# Arm_control_pull.net
KiCad netlist of a schematic drawn in Altium Designer
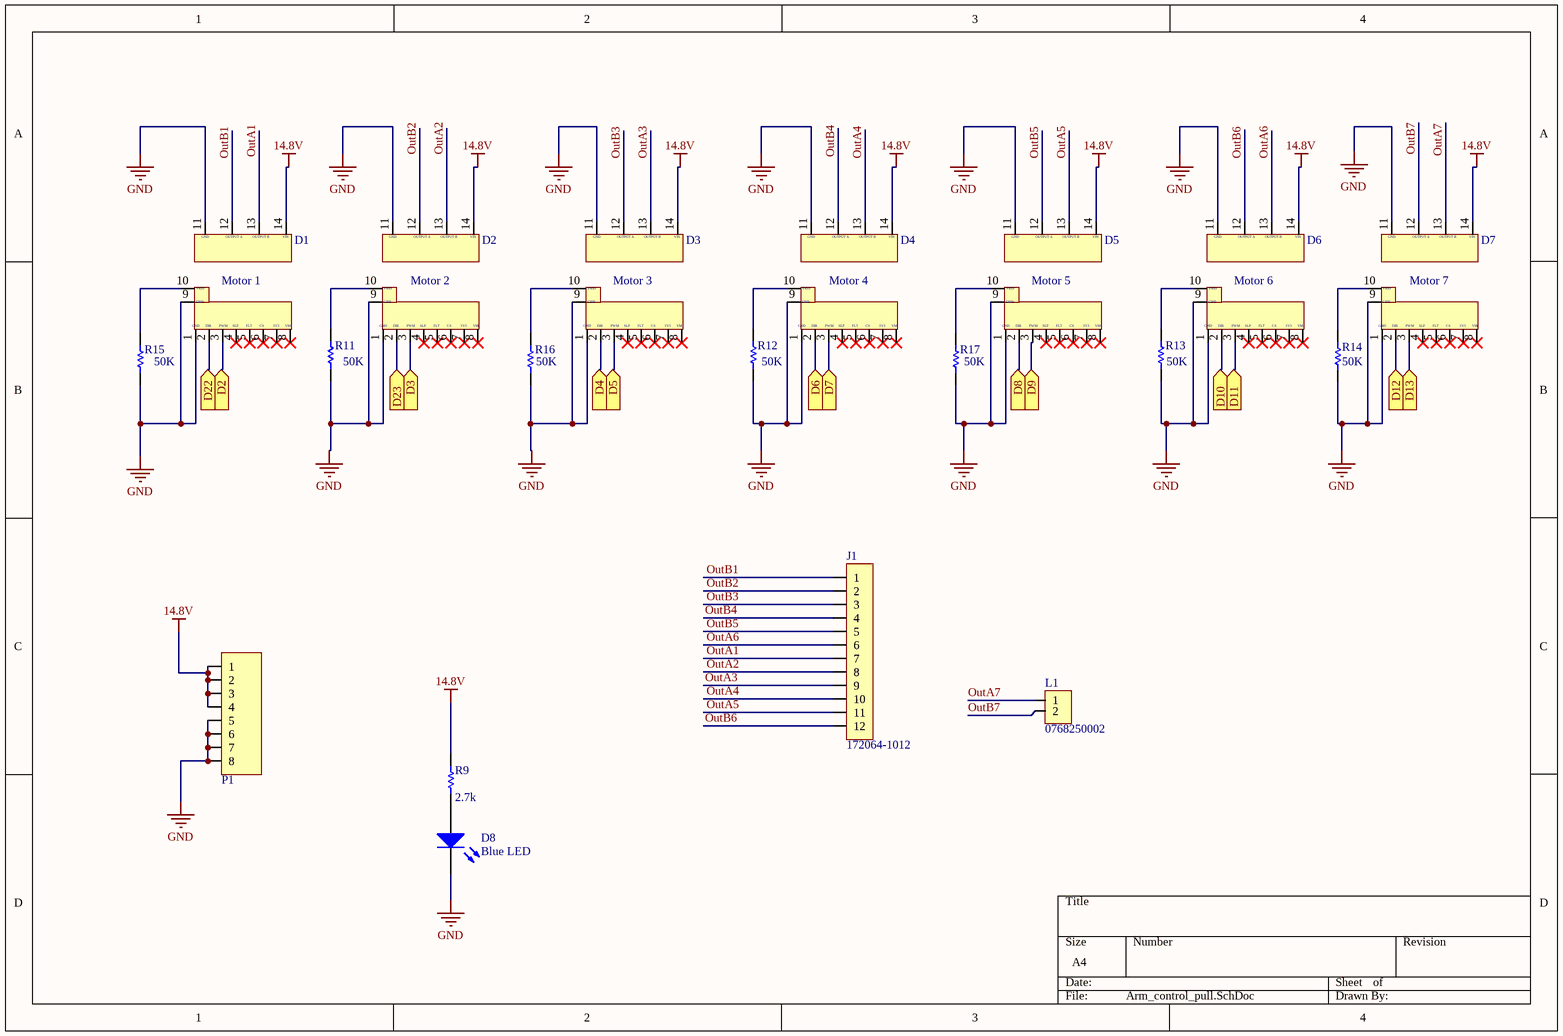
[diagram p0: Arm_control_pull.SchDoc]

(export (version "E")
  (design (tool "Eeschema 10.0.6"))
  (components
    (comp (ref "D1")
      (value "Pololu G2 High-Power Motor Driver 18v25")
      (footprint "POLOLU 18V25")
      (libsource (lib "RSX_Modules") (part "Pololu G2 High-Power Motor Driver 18v25"))
    )
    (comp (ref "D2")
      (value "Pololu G2 High-Power Motor Driver 18v25")
      (footprint "POLOLU 18V25")
      (libsource (lib "RSX_Modules") (part "Pololu G2 High-Power Motor Driver 18v25"))
    )
    (comp (ref "D3")
      (value "Pololu G2 High-Power Motor Driver 18v25")
      (footprint "POLOLU 18V25")
      (libsource (lib "RSX_Modules") (part "Pololu G2 High-Power Motor Driver 18v25"))
    )
    (comp (ref "D4")
      (value "Pololu G2 High-Power Motor Driver 18v25")
      (footprint "POLOLU 18V25")
      (libsource (lib "RSX_Modules") (part "Pololu G2 High-Power Motor Driver 18v25"))
    )
    (comp (ref "D5")
      (value "Pololu G2 High-Power Motor Driver 18v25")
      (footprint "POLOLU 18V25")
      (libsource (lib "RSX_Modules") (part "Pololu G2 High-Power Motor Driver 18v25"))
    )
    (comp (ref "D6")
      (value "Pololu G2 High-Power Motor Driver 18v25")
      (footprint "POLOLU 18V25")
      (libsource (lib "RSX_Modules") (part "Pololu G2 High-Power Motor Driver 18v25"))
    )
    (comp (ref "D7")
      (value "Pololu G2 High-Power Motor Driver 18v25")
      (footprint "POLOLU 18V25")
      (libsource (lib "RSX_Modules") (part "Pololu G2 High-Power Motor Driver 18v25"))
    )
    (comp (ref "D8")
      (value "Blue LED")
      (footprint "LTST-C171TBKT")
      (libsource (lib "RSX_Diodes") (part "Blue LED"))
    )
    (comp (ref "J1")
      (value "172064-1012")
      (footprint "172064-1012")
      (description "Conn Shrouded Header HDR 12 POS 5.7mm Solder RA Thru-Hole Tray")
      (libsource (lib "RSX_Connectors") (part "172064-1012"))
    )
    (comp (ref "L1")
      (value "0768250002")
      (footprint "MOLEX 0768250002")
      (description "Conn Power HDR 2 POS 5.7mm Solder RA Thru-Hole 2 Terminal 1 Port")
      (libsource (lib "RSX_Connectors") (part "0768250002"))
    )
    (comp (ref "P1")
      (value "Mini-Fit Jr 8 Pos RA")
      (footprint "MOLEX 172065-0208")
      (libsource (lib "RSX_Connectors") (part "Molex Mega-Fit 8pos Vert"))
    )
    (comp (ref "R9")
      (value "2.7k")
      (footprint "RESC1608X06N_0603")
      (description "Resistor")
      (fields (field (name "Comment") "Res1") (field (name "PUBLISHER") "Altium Limited"))
      (libsource (lib "RSX_Resistors") (part "Res1"))
    )
    (comp (ref "R11")
      (value "50K")
      (footprint "RESC1608X06N_0603")
      (description "Resistor")
      (fields (field (name "Comment") "Res1") (field (name "PUBLISHER") "Altium Limited"))
      (libsource (lib "RSX_Resistors") (part "Res1"))
    )
    (comp (ref "R12")
      (value "50K")
      (footprint "RESC1608X06N_0603")
      (description "Resistor")
      (fields (field (name "Comment") "Res1") (field (name "PUBLISHER") "Altium Limited"))
      (libsource (lib "RSX_Resistors") (part "Res1"))
    )
    (comp (ref "R13")
      (value "50K")
      (footprint "RESC1608X06N_0603")
      (description "Resistor")
      (fields (field (name "Comment") "Res1") (field (name "PUBLISHER") "Altium Limited"))
      (libsource (lib "RSX_Resistors") (part "Res1"))
    )
    (comp (ref "R14")
      (value "50K")
      (footprint "RESC1608X06N_0603")
      (description "Resistor")
      (fields (field (name "Comment") "Res1") (field (name "PUBLISHER") "Altium Limited"))
      (libsource (lib "RSX_Resistors") (part "Res1"))
    )
    (comp (ref "R15")
      (value "50K")
      (footprint "RESC1608X06N_0603")
      (description "Resistor")
      (fields (field (name "Comment") "Res1") (field (name "PUBLISHER") "Altium Limited"))
      (libsource (lib "RSX_Resistors") (part "Res1"))
    )
    (comp (ref "R16")
      (value "50K")
      (footprint "RESC1608X06N_0603")
      (description "Resistor")
      (fields (field (name "Comment") "Res1") (field (name "PUBLISHER") "Altium Limited"))
      (libsource (lib "RSX_Resistors") (part "Res1"))
    )
    (comp (ref "R17")
      (value "50K")
      (footprint "RESC1608X06N_0603")
      (description "Resistor")
      (fields (field (name "Comment") "Res1") (field (name "PUBLISHER") "Altium Limited"))
      (libsource (lib "RSX_Resistors") (part "Res1"))
    )
  )
  (nets
    (net (code "2") (name "/D2") (class "Default")
      (node (ref "D1") (pin "3") (pinfunction "3_3") (pintype "passive"))
    )
    (net (code "3") (name "/D3") (class "Default")
      (node (ref "D2") (pin "3") (pinfunction "3_3") (pintype "passive"))
    )
    (net (code "4") (name "/D4") (class "Default")
      (node (ref "D3") (pin "2") (pinfunction "2_2") (pintype "passive"))
    )
    (net (code "5") (name "/D5") (class "Default")
      (node (ref "D3") (pin "3") (pinfunction "3_3") (pintype "passive"))
    )
    (net (code "6") (name "/D6") (class "Default")
      (node (ref "D4") (pin "2") (pinfunction "2_2") (pintype "passive"))
    )
    (net (code "7") (name "/D7") (class "Default")
      (node (ref "D4") (pin "3") (pinfunction "3_3") (pintype "passive"))
    )
    (net (code "8") (name "/D8") (class "Default")
      (node (ref "D5") (pin "2") (pinfunction "2_2") (pintype "passive"))
    )
    (net (code "9") (name "/D9") (class "Default")
      (node (ref "D5") (pin "3") (pinfunction "3_3") (pintype "passive"))
    )
    (net (code "10") (name "/D10") (class "Default")
      (node (ref "D6") (pin "2") (pinfunction "2_2") (pintype "passive"))
    )
    (net (code "11") (name "/D11") (class "Default")
      (node (ref "D6") (pin "3") (pinfunction "3_3") (pintype "passive"))
    )
    (net (code "12") (name "/D12") (class "Default")
      (node (ref "D7") (pin "2") (pinfunction "2_2") (pintype "passive"))
    )
    (net (code "13") (name "/D13") (class "Default")
      (node (ref "D7") (pin "3") (pinfunction "3_3") (pintype "passive"))
    )
    (net (code "14") (name "/D22") (class "Default")
      (node (ref "D1") (pin "2") (pinfunction "2_2") (pintype "passive"))
    )
    (net (code "15") (name "/D23") (class "Default")
      (node (ref "D2") (pin "2") (pinfunction "2_2") (pintype "passive"))
    )
    (net (code "16") (name "/OutA1") (class "Default")
      (node (ref "D1") (pin "13") (pinfunction "13_13") (pintype "passive"))
      (node (ref "J1") (pin "7") (pinfunction "7_7") (pintype "passive"))
    )
    (net (code "17") (name "/OutA2") (class "Default")
      (node (ref "D2") (pin "13") (pinfunction "13_13") (pintype "passive"))
      (node (ref "J1") (pin "8") (pinfunction "8_8") (pintype "passive"))
    )
    (net (code "18") (name "/OutA3") (class "Default")
      (node (ref "D3") (pin "13") (pinfunction "13_13") (pintype "passive"))
      (node (ref "J1") (pin "9") (pinfunction "9_9") (pintype "passive"))
    )
    (net (code "19") (name "/OutA4") (class "Default")
      (node (ref "D4") (pin "13") (pinfunction "13_13") (pintype "passive"))
      (node (ref "J1") (pin "10") (pinfunction "10_10") (pintype "passive"))
    )
    (net (code "20") (name "/OutA5") (class "Default")
      (node (ref "D5") (pin "13") (pinfunction "13_13") (pintype "passive"))
      (node (ref "J1") (pin "11") (pinfunction "11_11") (pintype "passive"))
    )
    (net (code "21") (name "/OutA6") (class "Default")
      (node (ref "D6") (pin "13") (pinfunction "13_13") (pintype "passive"))
      (node (ref "J1") (pin "6") (pinfunction "6_6") (pintype "passive"))
    )
    (net (code "22") (name "/OutA7") (class "Default")
      (node (ref "D7") (pin "13") (pinfunction "13_13") (pintype "passive"))
      (node (ref "L1") (pin "1") (pinfunction "1_1") (pintype "passive"))
    )
    (net (code "23") (name "/OutB1") (class "Default")
      (node (ref "D1") (pin "12") (pinfunction "12_12") (pintype "passive"))
      (node (ref "J1") (pin "1") (pinfunction "1_1") (pintype "passive"))
    )
    (net (code "24") (name "/OutB2") (class "Default")
      (node (ref "D2") (pin "12") (pinfunction "12_12") (pintype "passive"))
      (node (ref "J1") (pin "2") (pinfunction "2_2") (pintype "passive"))
    )
    (net (code "25") (name "/OutB3") (class "Default")
      (node (ref "D3") (pin "12") (pinfunction "12_12") (pintype "passive"))
      (node (ref "J1") (pin "3") (pinfunction "3_3") (pintype "passive"))
    )
    (net (code "26") (name "/OutB4") (class "Default")
      (node (ref "D4") (pin "12") (pinfunction "12_12") (pintype "passive"))
      (node (ref "J1") (pin "4") (pinfunction "4_4") (pintype "passive"))
    )
    (net (code "27") (name "/OutB5") (class "Default")
      (node (ref "D5") (pin "12") (pinfunction "12_12") (pintype "passive"))
      (node (ref "J1") (pin "5") (pinfunction "5_5") (pintype "passive"))
    )
    (net (code "28") (name "/OutB6") (class "Default")
      (node (ref "D6") (pin "12") (pinfunction "12_12") (pintype "passive"))
      (node (ref "J1") (pin "12") (pinfunction "12_12") (pintype "passive"))
    )
    (net (code "29") (name "/OutB7") (class "Default")
      (node (ref "D7") (pin "12") (pinfunction "12_12") (pintype "passive"))
      (node (ref "L1") (pin "2") (pinfunction "2_2") (pintype "passive"))
    )
    (net (code "30") (name "14.8V") (class "Default")
      (node (ref "D1") (pin "14") (pinfunction "14_14") (pintype "passive"))
      (node (ref "D2") (pin "14") (pinfunction "14_14") (pintype "passive"))
      (node (ref "D3") (pin "14") (pinfunction "14_14") (pintype "passive"))
      (node (ref "D4") (pin "14") (pinfunction "14_14") (pintype "passive"))
      (node (ref "D5") (pin "14") (pinfunction "14_14") (pintype "passive"))
      (node (ref "D6") (pin "14") (pinfunction "14_14") (pintype "passive"))
      (node (ref "D7") (pin "14") (pinfunction "14_14") (pintype "passive"))
      (node (ref "P1") (pin "1") (pinfunction "1_1") (pintype "passive"))
      (node (ref "P1") (pin "2") (pinfunction "2_2") (pintype "passive"))
      (node (ref "P1") (pin "3") (pinfunction "3_3") (pintype "passive"))
      (node (ref "P1") (pin "4") (pinfunction "4_4") (pintype "passive"))
      (node (ref "R9") (pin "1") (pinfunction "1_1") (pintype "passive"))
    )
    (net (code "31") (name "GND") (class "Default")
      (node (ref "D1") (pin "1") (pinfunction "1_1") (pintype "passive"))
      (node (ref "D1") (pin "11") (pinfunction "11_11") (pintype "passive"))
      (node (ref "D1") (pin "9") (pinfunction "9_9") (pintype "passive"))
      (node (ref "D2") (pin "1") (pinfunction "1_1") (pintype "passive"))
      (node (ref "D2") (pin "11") (pinfunction "11_11") (pintype "passive"))
      (node (ref "D2") (pin "9") (pinfunction "9_9") (pintype "passive"))
      (node (ref "D3") (pin "1") (pinfunction "1_1") (pintype "passive"))
      (node (ref "D3") (pin "11") (pinfunction "11_11") (pintype "passive"))
      (node (ref "D3") (pin "9") (pinfunction "9_9") (pintype "passive"))
      (node (ref "D4") (pin "1") (pinfunction "1_1") (pintype "passive"))
      (node (ref "D4") (pin "11") (pinfunction "11_11") (pintype "passive"))
      (node (ref "D4") (pin "9") (pinfunction "9_9") (pintype "passive"))
      (node (ref "D5") (pin "1") (pinfunction "1_1") (pintype "passive"))
      (node (ref "D5") (pin "11") (pinfunction "11_11") (pintype "passive"))
      (node (ref "D5") (pin "9") (pinfunction "9_9") (pintype "passive"))
      (node (ref "D6") (pin "1") (pinfunction "1_1") (pintype "passive"))
      (node (ref "D6") (pin "11") (pinfunction "11_11") (pintype "passive"))
      (node (ref "D6") (pin "9") (pinfunction "9_9") (pintype "passive"))
      (node (ref "D7") (pin "1") (pinfunction "1_1") (pintype "passive"))
      (node (ref "D7") (pin "11") (pinfunction "11_11") (pintype "passive"))
      (node (ref "D7") (pin "9") (pinfunction "9_9") (pintype "passive"))
      (node (ref "D8") (pin "2") (pinfunction "K_2") (pintype "passive"))
      (node (ref "P1") (pin "5") (pinfunction "5_5") (pintype "passive"))
      (node (ref "P1") (pin "6") (pinfunction "6_6") (pintype "passive"))
      (node (ref "P1") (pin "7") (pinfunction "7_7") (pintype "passive"))
      (node (ref "P1") (pin "8") (pinfunction "8_8") (pintype "passive"))
      (node (ref "R11") (pin "1") (pinfunction "1_1") (pintype "passive"))
      (node (ref "R12") (pin "1") (pinfunction "1_1") (pintype "passive"))
      (node (ref "R13") (pin "1") (pinfunction "1_1") (pintype "passive"))
      (node (ref "R14") (pin "1") (pinfunction "1_1") (pintype "passive"))
      (node (ref "R15") (pin "1") (pinfunction "1_1") (pintype "passive"))
      (node (ref "R16") (pin "1") (pinfunction "1_1") (pintype "passive"))
      (node (ref "R17") (pin "1") (pinfunction "1_1") (pintype "passive"))
    )
    (net (code "32") (name "Net-(D1-Pad10)") (class "Default")
      (node (ref "D1") (pin "10") (pinfunction "10_10") (pintype "passive"))
      (node (ref "R15") (pin "2") (pinfunction "2_2") (pintype "passive"))
    )
    (net (code "33") (name "Net-(D2-Pad10)") (class "Default")
      (node (ref "D2") (pin "10") (pinfunction "10_10") (pintype "passive"))
      (node (ref "R11") (pin "2") (pinfunction "2_2") (pintype "passive"))
    )
    (net (code "34") (name "Net-(D3-Pad10)") (class "Default")
      (node (ref "D3") (pin "10") (pinfunction "10_10") (pintype "passive"))
      (node (ref "R16") (pin "2") (pinfunction "2_2") (pintype "passive"))
    )
    (net (code "35") (name "Net-(D4-Pad10)") (class "Default")
      (node (ref "D4") (pin "10") (pinfunction "10_10") (pintype "passive"))
      (node (ref "R12") (pin "2") (pinfunction "2_2") (pintype "passive"))
    )
    (net (code "36") (name "Net-(D5-Pad10)") (class "Default")
      (node (ref "D5") (pin "10") (pinfunction "10_10") (pintype "passive"))
      (node (ref "R17") (pin "2") (pinfunction "2_2") (pintype "passive"))
    )
    (net (code "37") (name "Net-(D6-Pad10)") (class "Default")
      (node (ref "D6") (pin "10") (pinfunction "10_10") (pintype "passive"))
      (node (ref "R13") (pin "2") (pinfunction "2_2") (pintype "passive"))
    )
    (net (code "38") (name "Net-(D7-Pad10)") (class "Default")
      (node (ref "D7") (pin "10") (pinfunction "10_10") (pintype "passive"))
      (node (ref "R14") (pin "2") (pinfunction "2_2") (pintype "passive"))
    )
    (net (code "39") (name "Net-(D8-A)") (class "Default")
      (node (ref "D8") (pin "1") (pinfunction "A_1") (pintype "passive"))
      (node (ref "R9") (pin "2") (pinfunction "2_2") (pintype "passive"))
    )
    (net (code "40") (name "unconnected-(D1-Pad4)") (class "Default")
      (node (ref "D1") (pin "4") (pinfunction "4_4") (pintype "passive+no_connect"))
    )
    (net (code "41") (name "unconnected-(D1-Pad5)") (class "Default")
      (node (ref "D1") (pin "5") (pinfunction "5_5") (pintype "passive+no_connect"))
    )
    (net (code "42") (name "unconnected-(D1-Pad6)") (class "Default")
      (node (ref "D1") (pin "6") (pinfunction "6_6") (pintype "passive+no_connect"))
    )
    (net (code "43") (name "unconnected-(D1-Pad7)") (class "Default")
      (node (ref "D1") (pin "7") (pinfunction "7_7") (pintype "passive+no_connect"))
    )
    (net (code "44") (name "unconnected-(D1-Pad8)") (class "Default")
      (node (ref "D1") (pin "8") (pinfunction "8_8") (pintype "passive+no_connect"))
    )
    (net (code "45") (name "unconnected-(D2-Pad4)") (class "Default")
      (node (ref "D2") (pin "4") (pinfunction "4_4") (pintype "passive+no_connect"))
    )
    (net (code "46") (name "unconnected-(D2-Pad5)") (class "Default")
      (node (ref "D2") (pin "5") (pinfunction "5_5") (pintype "passive+no_connect"))
    )
    (net (code "47") (name "unconnected-(D2-Pad6)") (class "Default")
      (node (ref "D2") (pin "6") (pinfunction "6_6") (pintype "passive+no_connect"))
    )
    (net (code "48") (name "unconnected-(D2-Pad7)") (class "Default")
      (node (ref "D2") (pin "7") (pinfunction "7_7") (pintype "passive+no_connect"))
    )
    (net (code "49") (name "unconnected-(D2-Pad8)") (class "Default")
      (node (ref "D2") (pin "8") (pinfunction "8_8") (pintype "passive+no_connect"))
    )
    (net (code "50") (name "unconnected-(D3-Pad4)") (class "Default")
      (node (ref "D3") (pin "4") (pinfunction "4_4") (pintype "passive+no_connect"))
    )
    (net (code "51") (name "unconnected-(D3-Pad5)") (class "Default")
      (node (ref "D3") (pin "5") (pinfunction "5_5") (pintype "passive+no_connect"))
    )
    (net (code "52") (name "unconnected-(D3-Pad6)") (class "Default")
      (node (ref "D3") (pin "6") (pinfunction "6_6") (pintype "passive+no_connect"))
    )
    (net (code "53") (name "unconnected-(D3-Pad7)") (class "Default")
      (node (ref "D3") (pin "7") (pinfunction "7_7") (pintype "passive+no_connect"))
    )
    (net (code "54") (name "unconnected-(D3-Pad8)") (class "Default")
      (node (ref "D3") (pin "8") (pinfunction "8_8") (pintype "passive+no_connect"))
    )
    (net (code "55") (name "unconnected-(D4-Pad4)") (class "Default")
      (node (ref "D4") (pin "4") (pinfunction "4_4") (pintype "passive+no_connect"))
    )
    (net (code "56") (name "unconnected-(D4-Pad5)") (class "Default")
      (node (ref "D4") (pin "5") (pinfunction "5_5") (pintype "passive+no_connect"))
    )
    (net (code "57") (name "unconnected-(D4-Pad6)") (class "Default")
      (node (ref "D4") (pin "6") (pinfunction "6_6") (pintype "passive+no_connect"))
    )
    (net (code "58") (name "unconnected-(D4-Pad7)") (class "Default")
      (node (ref "D4") (pin "7") (pinfunction "7_7") (pintype "passive+no_connect"))
    )
    (net (code "59") (name "unconnected-(D4-Pad8)") (class "Default")
      (node (ref "D4") (pin "8") (pinfunction "8_8") (pintype "passive+no_connect"))
    )
    (net (code "60") (name "unconnected-(D5-Pad4)") (class "Default")
      (node (ref "D5") (pin "4") (pinfunction "4_4") (pintype "passive+no_connect"))
    )
    (net (code "61") (name "unconnected-(D5-Pad5)") (class "Default")
      (node (ref "D5") (pin "5") (pinfunction "5_5") (pintype "passive+no_connect"))
    )
    (net (code "62") (name "unconnected-(D5-Pad6)") (class "Default")
      (node (ref "D5") (pin "6") (pinfunction "6_6") (pintype "passive+no_connect"))
    )
    (net (code "63") (name "unconnected-(D5-Pad7)") (class "Default")
      (node (ref "D5") (pin "7") (pinfunction "7_7") (pintype "passive+no_connect"))
    )
    (net (code "64") (name "unconnected-(D5-Pad8)") (class "Default")
      (node (ref "D5") (pin "8") (pinfunction "8_8") (pintype "passive+no_connect"))
    )
    (net (code "65") (name "unconnected-(D6-Pad4)") (class "Default")
      (node (ref "D6") (pin "4") (pinfunction "4_4") (pintype "passive+no_connect"))
    )
    (net (code "66") (name "unconnected-(D6-Pad5)") (class "Default")
      (node (ref "D6") (pin "5") (pinfunction "5_5") (pintype "passive+no_connect"))
    )
    (net (code "67") (name "unconnected-(D6-Pad6)") (class "Default")
      (node (ref "D6") (pin "6") (pinfunction "6_6") (pintype "passive+no_connect"))
    )
    (net (code "68") (name "unconnected-(D6-Pad7)") (class "Default")
      (node (ref "D6") (pin "7") (pinfunction "7_7") (pintype "passive+no_connect"))
    )
    (net (code "69") (name "unconnected-(D6-Pad8)") (class "Default")
      (node (ref "D6") (pin "8") (pinfunction "8_8") (pintype "passive+no_connect"))
    )
    (net (code "70") (name "unconnected-(D7-Pad4)") (class "Default")
      (node (ref "D7") (pin "4") (pinfunction "4_4") (pintype "passive+no_connect"))
    )
    (net (code "71") (name "unconnected-(D7-Pad5)") (class "Default")
      (node (ref "D7") (pin "5") (pinfunction "5_5") (pintype "passive+no_connect"))
    )
    (net (code "72") (name "unconnected-(D7-Pad6)") (class "Default")
      (node (ref "D7") (pin "6") (pinfunction "6_6") (pintype "passive+no_connect"))
    )
    (net (code "73") (name "unconnected-(D7-Pad7)") (class "Default")
      (node (ref "D7") (pin "7") (pinfunction "7_7") (pintype "passive+no_connect"))
    )
    (net (code "74") (name "unconnected-(D7-Pad8)") (class "Default")
      (node (ref "D7") (pin "8") (pinfunction "8_8") (pintype "passive+no_connect"))
    )
  )
)
